# buseds-hab.net
KiCad netlist of a schematic drawn in EAGLE
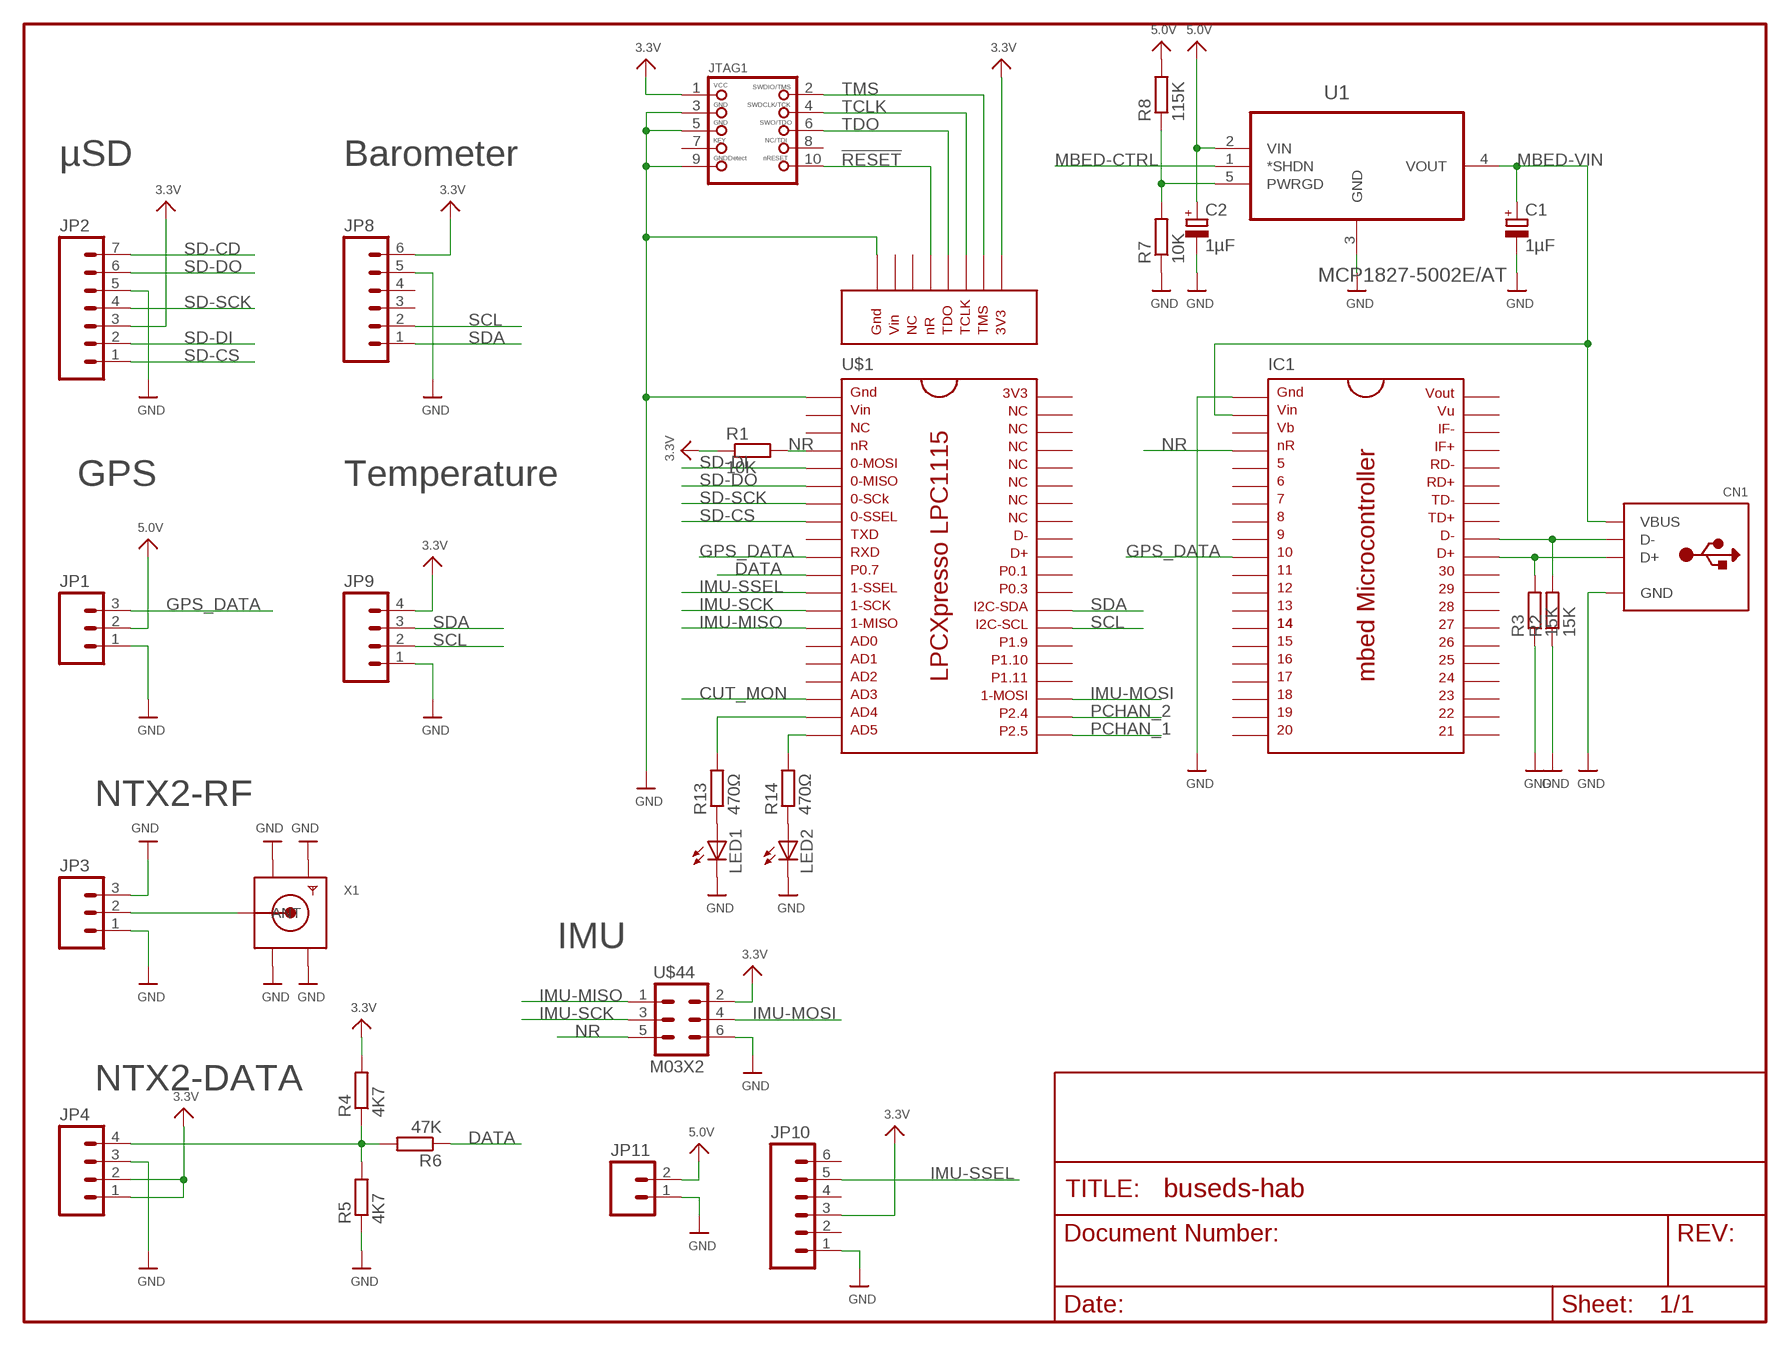
[diagram p0: schematic, sheet 1, part 1 of 2]
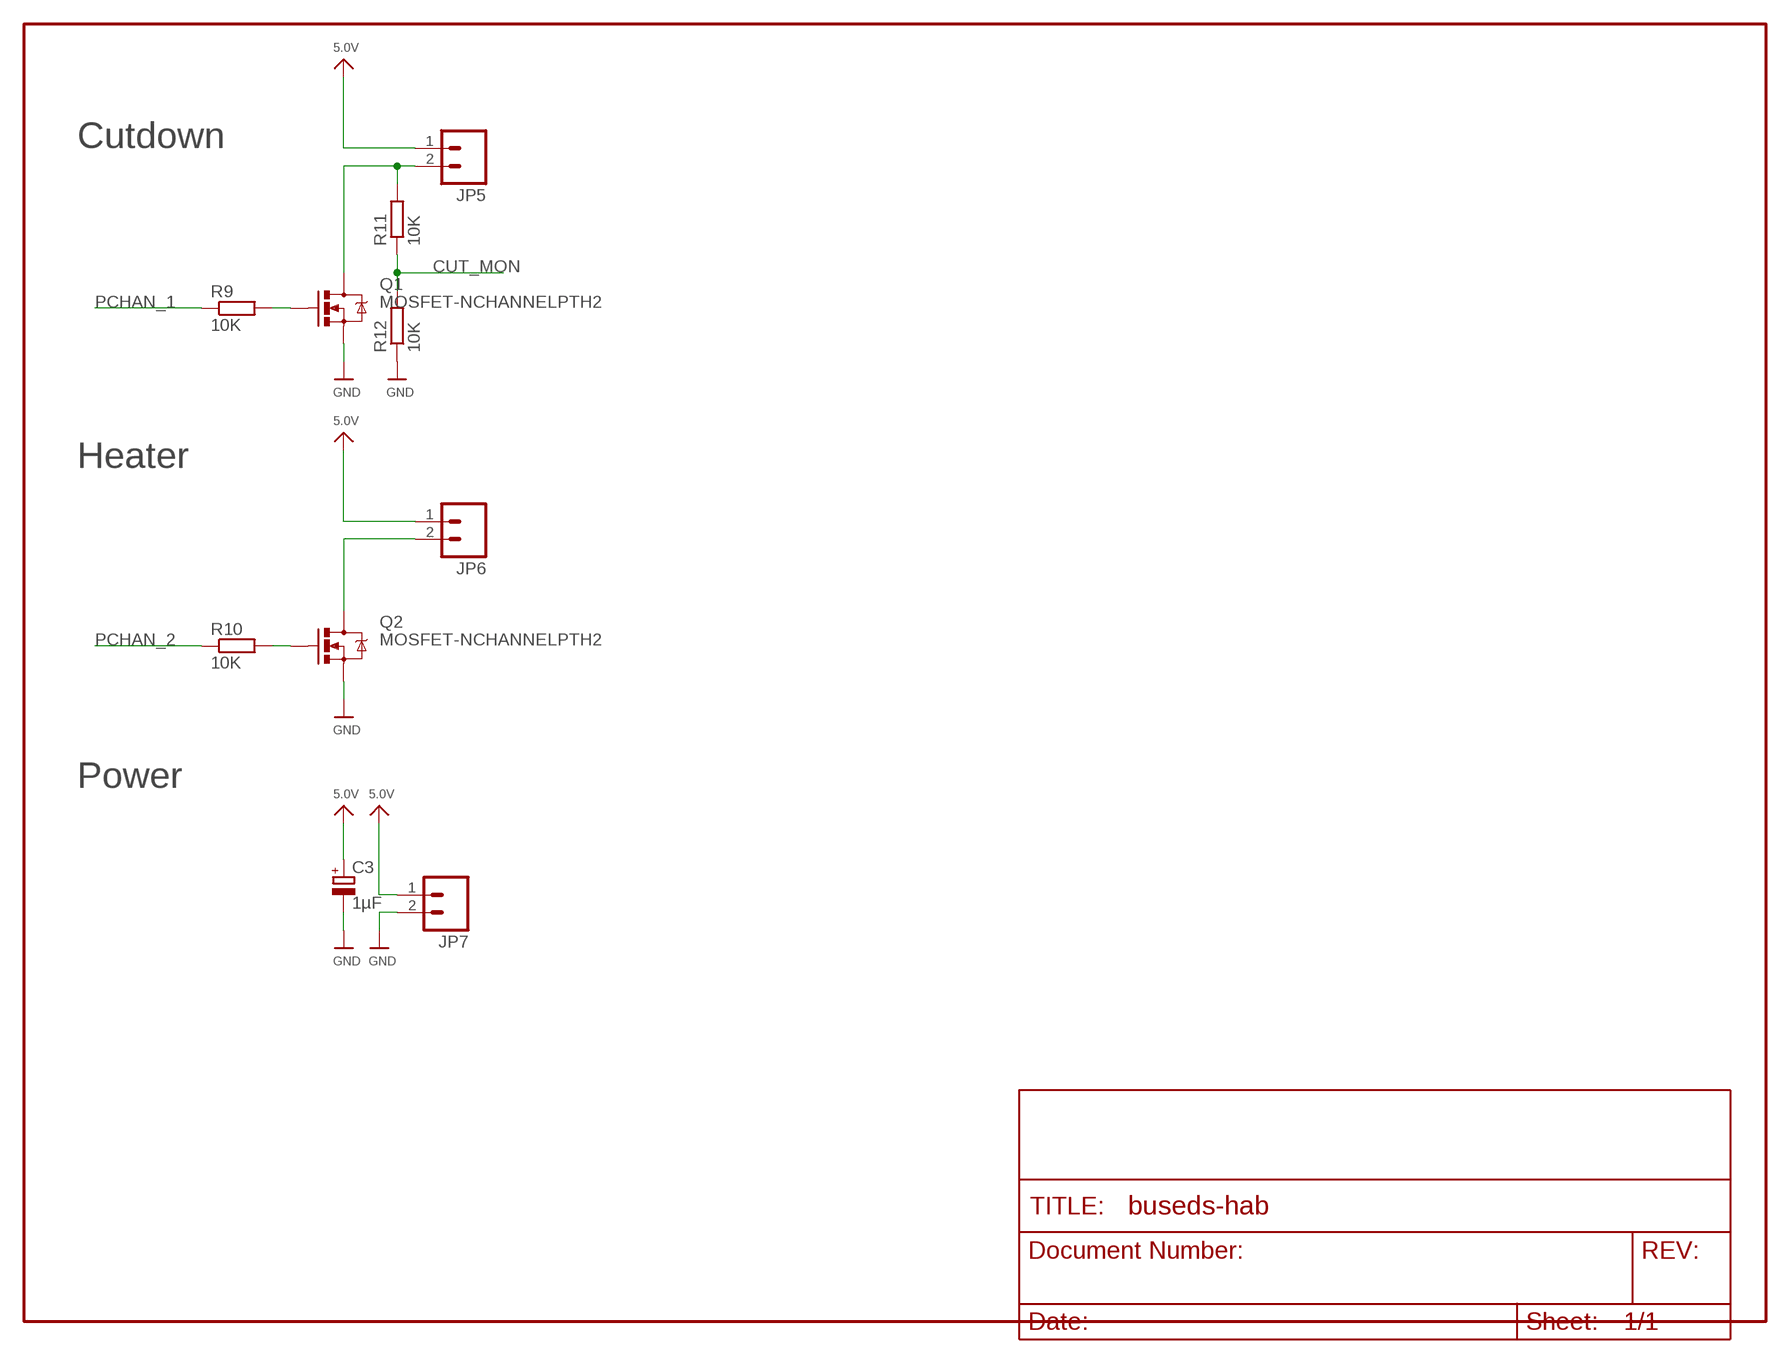
[diagram p1: schematic, sheet 1, part 2 of 2]

(export (version "E")
  (design (tool "Eeschema 10.0.6"))
  (components
    (comp (ref "C1")
      (value "1µF")
      (footprint "eagle-import:E2-5")
      (libsource (lib "eagle-import") (part "CPOL-EUE2-5"))
    )
    (comp (ref "C2")
      (value "1µF")
      (footprint "eagle-import:E2-5")
      (libsource (lib "eagle-import") (part "CPOL-EUE2-5"))
    )
    (comp (ref "C3")
      (value "1µF")
      (footprint "eagle-import:E2-5")
      (libsource (lib "eagle-import") (part "CPOL-EUE2-5"))
    )
    (comp (ref "CN1")
      (value "USB_TYPEAPTHFML")
      (footprint "eagle-import:USB_HOST-PTH")
      (libsource (lib "eagle-import") (part "USB_TYPEAPTHFML"))
    )
    (comp (ref "IC1")
      (value "MBED")
      (footprint "eagle-import:DIL40_0.9")
      (libsource (lib "eagle-import") (part "MBED"))
    )
    (comp (ref "JP1")
      (value "M03LOCK")
      (footprint "eagle-import:1X03_LOCK")
      (libsource (lib "eagle-import") (part "M03LOCK"))
    )
    (comp (ref "JP2")
      (value "M07LOCK")
      (footprint "eagle-import:1X07_LOCK")
      (libsource (lib "eagle-import") (part "M07LOCK"))
    )
    (comp (ref "JP3")
      (value "M03LOCK")
      (footprint "eagle-import:1X03_LOCK")
      (libsource (lib "eagle-import") (part "M03LOCK"))
    )
    (comp (ref "JP4")
      (value "M04LOCK")
      (footprint "eagle-import:1X04_LOCK")
      (libsource (lib "eagle-import") (part "M04LOCK"))
    )
    (comp (ref "JP5")
      (value "M023.5MM_LOCK")
      (footprint "eagle-import:SCREWTERMINAL-3.5MM-2_LOCK")
      (libsource (lib "eagle-import") (part "M023.5MM_LOCK"))
    )
    (comp (ref "JP6")
      (value "M023.5MM_LOCK")
      (footprint "eagle-import:SCREWTERMINAL-3.5MM-2_LOCK")
      (libsource (lib "eagle-import") (part "M023.5MM_LOCK"))
    )
    (comp (ref "JP7")
      (value "M023.5MM_LOCK")
      (footprint "eagle-import:SCREWTERMINAL-3.5MM-2_LOCK")
      (libsource (lib "eagle-import") (part "M023.5MM_LOCK"))
    )
    (comp (ref "JP8")
      (value "M06LOCK")
      (footprint "eagle-import:1X06_LOCK")
      (libsource (lib "eagle-import") (part "M06LOCK"))
    )
    (comp (ref "JP9")
      (value "M04LOCK")
      (footprint "eagle-import:1X04_LOCK")
      (libsource (lib "eagle-import") (part "M04LOCK"))
    )
    (comp (ref "JP10")
      (value "M06LOCK")
      (footprint "eagle-import:1X06_LOCK")
      (libsource (lib "eagle-import") (part "M06LOCK"))
    )
    (comp (ref "JP11")
      (value "M02LOCK")
      (footprint "eagle-import:1X02_LOCK")
      (libsource (lib "eagle-import") (part "M02LOCK"))
    )
    (comp (ref "JTAG1")
      (value "JTAG-CORTEXM3")
      (footprint "eagle-import:2X05_1.27MM")
      (libsource (lib "eagle-import") (part "JTAG-CORTEXM3"))
    )
    (comp (ref "LED1")
      (value "LED3MM")
      (footprint "eagle-import:LED3MM")
      (libsource (lib "eagle-import") (part "LED3MM"))
    )
    (comp (ref "LED2")
      (value "LED3MM")
      (footprint "eagle-import:LED3MM")
      (libsource (lib "eagle-import") (part "LED3MM"))
    )
    (comp (ref "Q1")
      (value "MOSFET-NCHANNELPTH2")
      (footprint "eagle-import:TO220V")
      (libsource (lib "eagle-import") (part "MOSFET-NCHANNELPTH2"))
    )
    (comp (ref "Q2")
      (value "MOSFET-NCHANNELPTH2")
      (footprint "eagle-import:TO220V")
      (libsource (lib "eagle-import") (part "MOSFET-NCHANNELPTH2"))
    )
    (comp (ref "R1")
      (value "10K")
      (footprint "eagle-import:0204_7")
      (libsource (lib "eagle-import") (part "R-EU_0204/7"))
    )
    (comp (ref "R2")
      (value "15K")
      (footprint "eagle-import:0204_7")
      (libsource (lib "eagle-import") (part "R-EU_0204/7"))
    )
    (comp (ref "R3")
      (value "15K")
      (footprint "eagle-import:0204_7")
      (libsource (lib "eagle-import") (part "R-EU_0204/7"))
    )
    (comp (ref "R4")
      (value "4K7")
      (footprint "eagle-import:0204_7")
      (libsource (lib "eagle-import") (part "R-EU_0204/7"))
    )
    (comp (ref "R5")
      (value "4K7")
      (footprint "eagle-import:0204_7")
      (libsource (lib "eagle-import") (part "R-EU_0204/7"))
    )
    (comp (ref "R6")
      (value "47K")
      (footprint "eagle-import:0204_7")
      (libsource (lib "eagle-import") (part "R-EU_0204/7"))
    )
    (comp (ref "R7")
      (value "10K")
      (footprint "eagle-import:0204_7")
      (libsource (lib "eagle-import") (part "R-EU_0204/7"))
    )
    (comp (ref "R8")
      (value "115K")
      (footprint "eagle-import:0204_7")
      (libsource (lib "eagle-import") (part "R-EU_0204/7"))
    )
    (comp (ref "R9")
      (value "10K")
      (footprint "eagle-import:0204_7")
      (libsource (lib "eagle-import") (part "R-EU_0204/7"))
    )
    (comp (ref "R10")
      (value "10K")
      (footprint "eagle-import:0204_7")
      (libsource (lib "eagle-import") (part "R-EU_0204/7"))
    )
    (comp (ref "R11")
      (value "10K")
      (footprint "eagle-import:0204_7")
      (libsource (lib "eagle-import") (part "R-EU_0204/7"))
    )
    (comp (ref "R12")
      (value "10K")
      (footprint "eagle-import:0204_7")
      (libsource (lib "eagle-import") (part "R-EU_0204/7"))
    )
    (comp (ref "R13")
      (value "470Ω")
      (footprint "eagle-import:0204_7")
      (libsource (lib "eagle-import") (part "R-EU_0204/7"))
    )
    (comp (ref "R14")
      (value "470Ω")
      (footprint "eagle-import:0204_7")
      (libsource (lib "eagle-import") (part "R-EU_0204/7"))
    )
    (comp (ref "U$1")
      (value "LPCXPRESSOLPC")
      (footprint "eagle-import:LPCXPRESSO")
      (libsource (lib "eagle-import") (part "LPCXPRESSOLPC"))
    )
    (comp (ref "U$44")
      (value "M03X2")
      (footprint "eagle-import:2X3_LOCK")
      (libsource (lib "eagle-import") (part "M03X2"))
    )
    (comp (ref "U1")
      (value "MCP1827-5002E/AT")
      (footprint "eagle-import:TO170P482X1024X3124-5P")
      (libsource (lib "eagle-import") (part "MCP1827-5002E/AT"))
    )
    (comp (ref "X1")
      (value "SMACONNECTOR")
      (footprint "eagle-import:SMA90_DIP")
      (libsource (lib "eagle-import") (part "SMACONNECTOR"))
    )
  )
  (nets
    (net (code "1") (name "/CUT_MON") (class "Default")
      (node (ref "R11") (pin "1") (pinfunction "1_1") (pintype "passive"))
      (node (ref "R12") (pin "2") (pinfunction "2_2") (pintype "passive"))
      (node (ref "U$1") (pin "18") (pinfunction "P$18_18") (pintype "bidirectional"))
    )
    (net (code "2") (name "/DATA") (class "Default")
      (node (ref "R6") (pin "1") (pinfunction "1_1") (pintype "passive"))
      (node (ref "U$1") (pin "11") (pinfunction "P$11_11") (pintype "bidirectional"))
    )
    (net (code "3") (name "/GPS_DATA") (class "Default")
      (node (ref "IC1") (pin "10") (pinfunction "P$10_10") (pintype "bidirectional"))
      (node (ref "JP1") (pin "3") (pinfunction "3_3") (pintype "passive"))
      (node (ref "U$1") (pin "10") (pinfunction "P$10_10") (pintype "bidirectional"))
    )
    (net (code "4") (name "/IMU-MISO") (class "Default")
      (node (ref "U$1") (pin "14") (pinfunction "P$14_14") (pintype "bidirectional"))
      (node (ref "U$44") (pin "1") (pinfunction "1_1") (pintype "passive"))
    )
    (net (code "5") (name "/IMU-MOSI") (class "Default")
      (node (ref "U$1") (pin "23") (pinfunction "P$23_23") (pintype "bidirectional"))
      (node (ref "U$44") (pin "4") (pinfunction "4_4") (pintype "passive"))
    )
    (net (code "6") (name "/IMU-SCK") (class "Default")
      (node (ref "U$1") (pin "13") (pinfunction "P$13_13") (pintype "bidirectional"))
      (node (ref "U$44") (pin "3") (pinfunction "3_3") (pintype "passive"))
    )
    (net (code "7") (name "/IMU-SSEL") (class "Default")
      (node (ref "JP10") (pin "5") (pinfunction "5_5") (pintype "passive"))
      (node (ref "U$1") (pin "12") (pinfunction "P$12_12") (pintype "bidirectional"))
    )
    (net (code "8") (name "/MBED-CTRL") (class "Default")
      (node (ref "U1") (pin "1") (pinfunction "*SHDN_1") (pintype "input"))
    )
    (net (code "9") (name "/MBED-VIN") (class "Default")
      (node (ref "C1") (pin "+") (pinfunction "+_+") (pintype "passive"))
      (node (ref "CN1") (pin "VBUS") (pinfunction "VBUS_VBUS") (pintype "power_in"))
      (node (ref "IC1") (pin "2") (pinfunction "P$2_2") (pintype "bidirectional"))
      (node (ref "U1") (pin "4") (pinfunction "VOUT_4") (pintype "output"))
    )
    (net (code "10") (name "/NR") (class "Default")
      (node (ref "IC1") (pin "4") (pinfunction "P$4_4") (pintype "bidirectional"))
      (node (ref "R1") (pin "2") (pinfunction "2_2") (pintype "passive"))
      (node (ref "U$1") (pin "4") (pinfunction "P$4_4") (pintype "bidirectional"))
      (node (ref "U$44") (pin "5") (pinfunction "5_5") (pintype "passive"))
    )
    (net (code "11") (name "/PCHAN_1") (class "Default")
      (node (ref "R9") (pin "1") (pinfunction "1_1") (pintype "passive"))
      (node (ref "U$1") (pin "21") (pinfunction "P$21_21") (pintype "bidirectional"))
    )
    (net (code "12") (name "/PCHAN_2") (class "Default")
      (node (ref "R10") (pin "1") (pinfunction "1_1") (pintype "passive"))
      (node (ref "U$1") (pin "22") (pinfunction "P$22_22") (pintype "bidirectional"))
    )
    (net (code "13") (name "/SCL") (class "Default")
      (node (ref "JP8") (pin "2") (pinfunction "2_2") (pintype "passive"))
      (node (ref "JP9") (pin "2") (pinfunction "2_2") (pintype "passive"))
      (node (ref "U$1") (pin "27") (pinfunction "P$27_27") (pintype "bidirectional"))
    )
    (net (code "14") (name "/SD-CD") (class "Default")
      (node (ref "JP2") (pin "7") (pinfunction "7_7") (pintype "passive"))
    )
    (net (code "15") (name "/SD-CS") (class "Default")
      (node (ref "JP2") (pin "1") (pinfunction "1_1") (pintype "passive"))
      (node (ref "U$1") (pin "8") (pinfunction "P$8_8") (pintype "bidirectional"))
    )
    (net (code "16") (name "/SD-DI") (class "Default")
      (node (ref "JP2") (pin "2") (pinfunction "2_2") (pintype "passive"))
      (node (ref "U$1") (pin "5") (pinfunction "P$5_5") (pintype "bidirectional"))
    )
    (net (code "17") (name "/SD-DO") (class "Default")
      (node (ref "JP2") (pin "6") (pinfunction "6_6") (pintype "passive"))
      (node (ref "U$1") (pin "6") (pinfunction "P$6_6") (pintype "bidirectional"))
    )
    (net (code "18") (name "/SD-SCK") (class "Default")
      (node (ref "JP2") (pin "4") (pinfunction "4_4") (pintype "passive"))
      (node (ref "U$1") (pin "7") (pinfunction "P$7_7") (pintype "bidirectional"))
    )
    (net (code "19") (name "/SDA") (class "Default")
      (node (ref "JP8") (pin "1") (pinfunction "1_1") (pintype "passive"))
      (node (ref "JP9") (pin "3") (pinfunction "3_3") (pintype "passive"))
      (node (ref "U$1") (pin "28") (pinfunction "P$28_28") (pintype "bidirectional"))
    )
    (net (code "20") (name "/TCLK") (class "Default")
      (node (ref "JTAG1") (pin "4") (pinfunction "4_4") (pintype "passive"))
      (node (ref "U$1") (pin "P-3") (pinfunction "P-3_P-3") (pintype "bidirectional"))
    )
    (net (code "21") (name "/TDO") (class "Default")
      (node (ref "JTAG1") (pin "6") (pinfunction "6_6") (pintype "passive"))
      (node (ref "U$1") (pin "P-4") (pinfunction "P-4_P-4") (pintype "bidirectional"))
    )
    (net (code "22") (name "/TMS") (class "Default")
      (node (ref "JTAG1") (pin "2") (pinfunction "2_2") (pintype "passive"))
      (node (ref "U$1") (pin "P-2") (pinfunction "P-2_P-2") (pintype "bidirectional"))
    )
    (net (code "23") (name "/~{RESET}") (class "Default")
      (node (ref "JTAG1") (pin "10") (pinfunction "10_10") (pintype "passive"))
      (node (ref "U$1") (pin "P-5") (pinfunction "P-5_P-5") (pintype "bidirectional"))
    )
    (net (code "24") (name "3.3V") (class "Default")
      (node (ref "JP10") (pin "3") (pinfunction "3_3") (pintype "passive"))
      (node (ref "JP2") (pin "3") (pinfunction "3_3") (pintype "passive"))
      (node (ref "JP4") (pin "1") (pinfunction "1_1") (pintype "passive"))
      (node (ref "JP4") (pin "2") (pinfunction "2_2") (pintype "passive"))
      (node (ref "JP8") (pin "6") (pinfunction "6_6") (pintype "passive"))
      (node (ref "JP9") (pin "4") (pinfunction "4_4") (pintype "passive"))
      (node (ref "JTAG1") (pin "1") (pinfunction "1_1") (pintype "passive"))
      (node (ref "R1") (pin "1") (pinfunction "1_1") (pintype "passive"))
      (node (ref "R4") (pin "2") (pinfunction "2_2") (pintype "passive"))
      (node (ref "U$1") (pin "P-1") (pinfunction "P-1_P-1") (pintype "bidirectional"))
      (node (ref "U$44") (pin "2") (pinfunction "2_2") (pintype "passive"))
    )
    (net (code "25") (name "5.0V") (class "Default")
      (node (ref "C2") (pin "+") (pinfunction "+_+") (pintype "passive"))
      (node (ref "C3") (pin "+") (pinfunction "+_+") (pintype "passive"))
      (node (ref "JP1") (pin "2") (pinfunction "2_2") (pintype "passive"))
      (node (ref "JP11") (pin "2") (pinfunction "2_2") (pintype "passive"))
      (node (ref "JP5") (pin "1") (pinfunction "1_1") (pintype "passive"))
      (node (ref "JP6") (pin "1") (pinfunction "1_1") (pintype "passive"))
      (node (ref "JP7") (pin "1") (pinfunction "1_1") (pintype "passive"))
      (node (ref "R8") (pin "2") (pinfunction "2_2") (pintype "passive"))
      (node (ref "U1") (pin "2") (pinfunction "VIN_2") (pintype "input"))
    )
    (net (code "26") (name "GND") (class "Default")
      (node (ref "C1") (pin "-") (pinfunction "-_-") (pintype "passive"))
      (node (ref "C2") (pin "-") (pinfunction "-_-") (pintype "passive"))
      (node (ref "C3") (pin "-") (pinfunction "-_-") (pintype "passive"))
      (node (ref "CN1") (pin "GND") (pinfunction "GND_GND") (pintype "power_in"))
      (node (ref "IC1") (pin "1") (pinfunction "P$1_1") (pintype "bidirectional"))
      (node (ref "JP1") (pin "1") (pinfunction "1_1") (pintype "passive"))
      (node (ref "JP10") (pin "1") (pinfunction "1_1") (pintype "passive"))
      (node (ref "JP11") (pin "1") (pinfunction "1_1") (pintype "passive"))
      (node (ref "JP2") (pin "5") (pinfunction "5_5") (pintype "passive"))
      (node (ref "JP3") (pin "1") (pinfunction "1_1") (pintype "passive"))
      (node (ref "JP3") (pin "3") (pinfunction "3_3") (pintype "passive"))
      (node (ref "JP4") (pin "3") (pinfunction "3_3") (pintype "passive"))
      (node (ref "JP7") (pin "2") (pinfunction "2_2") (pintype "passive"))
      (node (ref "JP8") (pin "5") (pinfunction "5_5") (pintype "passive"))
      (node (ref "JP9") (pin "1") (pinfunction "1_1") (pintype "passive"))
      (node (ref "JTAG1") (pin "3") (pinfunction "3_3") (pintype "passive"))
      (node (ref "JTAG1") (pin "5") (pinfunction "5_5") (pintype "passive"))
      (node (ref "JTAG1") (pin "9") (pinfunction "9_9") (pintype "passive"))
      (node (ref "LED1") (pin "K") (pinfunction "C_K") (pintype "passive"))
      (node (ref "LED2") (pin "K") (pinfunction "C_K") (pintype "passive"))
      (node (ref "Q1") (pin "3") (pinfunction "S_3") (pintype "passive"))
      (node (ref "Q2") (pin "3") (pinfunction "S_3") (pintype "passive"))
      (node (ref "R12") (pin "1") (pinfunction "1_1") (pintype "passive"))
      (node (ref "R2") (pin "1") (pinfunction "1_1") (pintype "passive"))
      (node (ref "R3") (pin "1") (pinfunction "1_1") (pintype "passive"))
      (node (ref "R5") (pin "1") (pinfunction "1_1") (pintype "passive"))
      (node (ref "R7") (pin "1") (pinfunction "1_1") (pintype "passive"))
      (node (ref "U$1") (pin "1") (pinfunction "P$1_1") (pintype "bidirectional"))
      (node (ref "U$1") (pin "P-8") (pinfunction "P-8_P-8") (pintype "bidirectional"))
      (node (ref "U$44") (pin "6") (pinfunction "6_6") (pintype "passive"))
      (node (ref "U1") (pin "3") (pinfunction "GND_3") (pintype "passive"))
      (node (ref "X1") (pin "GND1") (pinfunction "GND1_GND1") (pintype "power_in"))
      (node (ref "X1") (pin "GND2") (pinfunction "GND2_GND2") (pintype "power_in"))
      (node (ref "X1") (pin "GND3") (pinfunction "GND3_GND3") (pintype "power_in"))
      (node (ref "X1") (pin "GND4") (pinfunction "GND4_GND4") (pintype "power_in"))
    )
    (net (code "27") (name "Net-(IC1-P$31)") (class "Default")
      (node (ref "CN1") (pin "D+") (pinfunction "D+_D+") (pintype "bidirectional"))
      (node (ref "IC1") (pin "31") (pinfunction "P$31_31") (pintype "bidirectional"))
      (node (ref "R3") (pin "2") (pinfunction "2_2") (pintype "passive"))
    )
    (net (code "28") (name "Net-(IC1-P$32)") (class "Default")
      (node (ref "CN1") (pin "D-") (pinfunction "D-_D-") (pintype "bidirectional"))
      (node (ref "IC1") (pin "32") (pinfunction "P$32_32") (pintype "bidirectional"))
      (node (ref "R2") (pin "2") (pinfunction "2_2") (pintype "passive"))
    )
    (net (code "29") (name "Net-(JP4-Pad4)") (class "Default")
      (node (ref "JP4") (pin "4") (pinfunction "4_4") (pintype "passive"))
      (node (ref "R4") (pin "1") (pinfunction "1_1") (pintype "passive"))
      (node (ref "R5") (pin "2") (pinfunction "2_2") (pintype "passive"))
      (node (ref "R6") (pin "2") (pinfunction "2_2") (pintype "passive"))
    )
    (net (code "30") (name "Net-(LED1-PadA)") (class "Default")
      (node (ref "LED1") (pin "A") (pinfunction "A_A") (pintype "passive"))
      (node (ref "R13") (pin "1") (pinfunction "1_1") (pintype "passive"))
    )
    (net (code "31") (name "Net-(LED2-PadA)") (class "Default")
      (node (ref "LED2") (pin "A") (pinfunction "A_A") (pintype "passive"))
      (node (ref "R14") (pin "1") (pinfunction "1_1") (pintype "passive"))
    )
    (net (code "32") (name "Net-(Q1-D)") (class "Default")
      (node (ref "JP5") (pin "2") (pinfunction "2_2") (pintype "passive"))
      (node (ref "Q1") (pin "2") (pinfunction "D_2") (pintype "passive"))
      (node (ref "R11") (pin "2") (pinfunction "2_2") (pintype "passive"))
    )
    (net (code "33") (name "Net-(Q1-G)") (class "Default")
      (node (ref "Q1") (pin "1") (pinfunction "G_1") (pintype "passive"))
      (node (ref "R9") (pin "2") (pinfunction "2_2") (pintype "passive"))
    )
    (net (code "34") (name "Net-(Q2-D)") (class "Default")
      (node (ref "JP6") (pin "2") (pinfunction "2_2") (pintype "passive"))
      (node (ref "Q2") (pin "2") (pinfunction "D_2") (pintype "passive"))
    )
    (net (code "35") (name "Net-(Q2-G)") (class "Default")
      (node (ref "Q2") (pin "1") (pinfunction "G_1") (pintype "passive"))
      (node (ref "R10") (pin "2") (pinfunction "2_2") (pintype "passive"))
    )
    (net (code "36") (name "Net-(U$1-P$19)") (class "Default")
      (node (ref "R13") (pin "2") (pinfunction "2_2") (pintype "passive"))
      (node (ref "U$1") (pin "19") (pinfunction "P$19_19") (pintype "bidirectional"))
    )
    (net (code "37") (name "Net-(U$1-P$20)") (class "Default")
      (node (ref "R14") (pin "2") (pinfunction "2_2") (pintype "passive"))
      (node (ref "U$1") (pin "20") (pinfunction "P$20_20") (pintype "bidirectional"))
    )
    (net (code "38") (name "Net-(U1-PWRGD)") (class "Default")
      (node (ref "R7") (pin "2") (pinfunction "2_2") (pintype "passive"))
      (node (ref "R8") (pin "1") (pinfunction "1_1") (pintype "passive"))
      (node (ref "U1") (pin "5") (pinfunction "PWRGD_5") (pintype "input"))
    )
    (net (code "39") (name "Net-(X1-ANT)") (class "Default")
      (node (ref "JP3") (pin "2") (pinfunction "2_2") (pintype "passive"))
      (node (ref "X1") (pin "ANTENNA") (pinfunction "ANT_ANTENNA") (pintype "bidirectional"))
    )
    (net (code "40") (name "unconnected-(IC1-P$3-Pad3)") (class "Default")
      (node (ref "IC1") (pin "3") (pinfunction "P$3_3") (pintype "bidirectional"))
    )
    (net (code "41") (name "unconnected-(IC1-P$5-Pad5)") (class "Default")
      (node (ref "IC1") (pin "5") (pinfunction "P$5_5") (pintype "bidirectional"))
    )
    (net (code "42") (name "unconnected-(IC1-P$6-Pad6)") (class "Default")
      (node (ref "IC1") (pin "6") (pinfunction "P$6_6") (pintype "bidirectional"))
    )
    (net (code "43") (name "unconnected-(IC1-P$7-Pad7)") (class "Default")
      (node (ref "IC1") (pin "7") (pinfunction "P$7_7") (pintype "bidirectional"))
    )
    (net (code "44") (name "unconnected-(IC1-P$8-Pad8)") (class "Default")
      (node (ref "IC1") (pin "8") (pinfunction "P$8_8") (pintype "bidirectional"))
    )
    (net (code "45") (name "unconnected-(IC1-P$9-Pad9)") (class "Default")
      (node (ref "IC1") (pin "9") (pinfunction "P$9_9") (pintype "bidirectional"))
    )
    (net (code "46") (name "unconnected-(IC1-P$11-Pad11)") (class "Default")
      (node (ref "IC1") (pin "11") (pinfunction "P$11_11") (pintype "bidirectional"))
    )
    (net (code "47") (name "unconnected-(IC1-P$12-Pad12)") (class "Default")
      (node (ref "IC1") (pin "12") (pinfunction "P$12_12") (pintype "bidirectional"))
    )
    (net (code "48") (name "unconnected-(IC1-P$13-Pad13)") (class "Default")
      (node (ref "IC1") (pin "13") (pinfunction "P$13_13") (pintype "bidirectional"))
    )
    (net (code "49") (name "unconnected-(IC1-P$14-Pad14)") (class "Default")
      (node (ref "IC1") (pin "14") (pinfunction "P$14_14") (pintype "bidirectional"))
    )
    (net (code "50") (name "unconnected-(IC1-P$15-Pad15)") (class "Default")
      (node (ref "IC1") (pin "15") (pinfunction "P$15_15") (pintype "bidirectional"))
    )
    (net (code "51") (name "unconnected-(IC1-P$16-Pad16)") (class "Default")
      (node (ref "IC1") (pin "16") (pinfunction "P$16_16") (pintype "bidirectional"))
    )
    (net (code "52") (name "unconnected-(IC1-P$17-Pad17)") (class "Default")
      (node (ref "IC1") (pin "17") (pinfunction "P$17_17") (pintype "bidirectional"))
    )
    (net (code "53") (name "unconnected-(IC1-P$18-Pad18)") (class "Default")
      (node (ref "IC1") (pin "18") (pinfunction "P$18_18") (pintype "bidirectional"))
    )
    (net (code "54") (name "unconnected-(IC1-P$19-Pad19)") (class "Default")
      (node (ref "IC1") (pin "19") (pinfunction "P$19_19") (pintype "bidirectional"))
    )
    (net (code "55") (name "unconnected-(IC1-P$20-Pad20)") (class "Default")
      (node (ref "IC1") (pin "20") (pinfunction "P$20_20") (pintype "bidirectional"))
    )
    (net (code "56") (name "unconnected-(IC1-P$21-Pad21)") (class "Default")
      (node (ref "IC1") (pin "21") (pinfunction "P$21_21") (pintype "bidirectional"))
    )
    (net (code "57") (name "unconnected-(IC1-P$22-Pad22)") (class "Default")
      (node (ref "IC1") (pin "22") (pinfunction "P$22_22") (pintype "bidirectional"))
    )
    (net (code "58") (name "unconnected-(IC1-P$23-Pad23)") (class "Default")
      (node (ref "IC1") (pin "23") (pinfunction "P$23_23") (pintype "bidirectional"))
    )
    (net (code "59") (name "unconnected-(IC1-P$24-Pad24)") (class "Default")
      (node (ref "IC1") (pin "24") (pinfunction "P$24_24") (pintype "bidirectional"))
    )
    (net (code "60") (name "unconnected-(IC1-P$25-Pad25)") (class "Default")
      (node (ref "IC1") (pin "25") (pinfunction "P$25_25") (pintype "bidirectional"))
    )
    (net (code "61") (name "unconnected-(IC1-P$26-Pad26)") (class "Default")
      (node (ref "IC1") (pin "26") (pinfunction "P$26_26") (pintype "bidirectional"))
    )
    (net (code "62") (name "unconnected-(IC1-P$27-Pad27)") (class "Default")
      (node (ref "IC1") (pin "27") (pinfunction "P$27_27") (pintype "bidirectional"))
    )
    (net (code "63") (name "unconnected-(IC1-P$28-Pad28)") (class "Default")
      (node (ref "IC1") (pin "28") (pinfunction "P$28_28") (pintype "bidirectional"))
    )
    (net (code "64") (name "unconnected-(IC1-P$29-Pad29)") (class "Default")
      (node (ref "IC1") (pin "29") (pinfunction "P$29_29") (pintype "bidirectional"))
    )
    (net (code "65") (name "unconnected-(IC1-P$30-Pad30)") (class "Default")
      (node (ref "IC1") (pin "30") (pinfunction "P$30_30") (pintype "bidirectional"))
    )
    (net (code "66") (name "unconnected-(IC1-P$33-Pad33)") (class "Default")
      (node (ref "IC1") (pin "33") (pinfunction "P$33_33") (pintype "bidirectional"))
    )
    (net (code "67") (name "unconnected-(IC1-P$34-Pad34)") (class "Default")
      (node (ref "IC1") (pin "34") (pinfunction "P$34_34") (pintype "bidirectional"))
    )
    (net (code "68") (name "unconnected-(IC1-P$35-Pad35)") (class "Default")
      (node (ref "IC1") (pin "35") (pinfunction "P$35_35") (pintype "bidirectional"))
    )
    (net (code "69") (name "unconnected-(IC1-P$36-Pad36)") (class "Default")
      (node (ref "IC1") (pin "36") (pinfunction "P$36_36") (pintype "bidirectional"))
    )
    (net (code "70") (name "unconnected-(IC1-P$37-Pad37)") (class "Default")
      (node (ref "IC1") (pin "37") (pinfunction "P$37_37") (pintype "bidirectional"))
    )
    (net (code "71") (name "unconnected-(IC1-P$38-Pad38)") (class "Default")
      (node (ref "IC1") (pin "38") (pinfunction "P$38_38") (pintype "bidirectional"))
    )
    (net (code "72") (name "unconnected-(IC1-P$39-Pad39)") (class "Default")
      (node (ref "IC1") (pin "39") (pinfunction "P$39_39") (pintype "bidirectional"))
    )
    (net (code "73") (name "unconnected-(IC1-P$40-Pad40)") (class "Default")
      (node (ref "IC1") (pin "40") (pinfunction "P$40_40") (pintype "bidirectional"))
    )
    (net (code "74") (name "unconnected-(JP8-Pad3)") (class "Default")
      (node (ref "JP8") (pin "3") (pinfunction "3_3") (pintype "passive"))
    )
    (net (code "75") (name "unconnected-(JP8-Pad4)") (class "Default")
      (node (ref "JP8") (pin "4") (pinfunction "4_4") (pintype "passive"))
    )
    (net (code "76") (name "unconnected-(JP10-Pad2)") (class "Default")
      (node (ref "JP10") (pin "2") (pinfunction "2_2") (pintype "passive"))
    )
    (net (code "77") (name "unconnected-(JP10-Pad4)") (class "Default")
      (node (ref "JP10") (pin "4") (pinfunction "4_4") (pintype "passive"))
    )
    (net (code "78") (name "unconnected-(JP10-Pad6)") (class "Default")
      (node (ref "JP10") (pin "6") (pinfunction "6_6") (pintype "passive"))
    )
    (net (code "79") (name "unconnected-(JTAG1-Pad7)") (class "Default")
      (node (ref "JTAG1") (pin "7") (pinfunction "7_7") (pintype "passive"))
    )
    (net (code "80") (name "unconnected-(JTAG1-Pad8)") (class "Default")
      (node (ref "JTAG1") (pin "8") (pinfunction "8_8") (pintype "passive"))
    )
    (net (code "81") (name "unconnected-(U$1-P$2-Pad2)") (class "Default")
      (node (ref "U$1") (pin "2") (pinfunction "P$2_2") (pintype "bidirectional"))
    )
    (net (code "82") (name "unconnected-(U$1-P$3-Pad3)") (class "Default")
      (node (ref "U$1") (pin "3") (pinfunction "P$3_3") (pintype "bidirectional"))
    )
    (net (code "83") (name "unconnected-(U$1-P$9-Pad9)") (class "Default")
      (node (ref "U$1") (pin "9") (pinfunction "P$9_9") (pintype "bidirectional"))
    )
    (net (code "84") (name "unconnected-(U$1-P$15-Pad15)") (class "Default")
      (node (ref "U$1") (pin "15") (pinfunction "P$15_15") (pintype "bidirectional"))
    )
    (net (code "85") (name "unconnected-(U$1-P$16-Pad16)") (class "Default")
      (node (ref "U$1") (pin "16") (pinfunction "P$16_16") (pintype "bidirectional"))
    )
    (net (code "86") (name "unconnected-(U$1-P$17-Pad17)") (class "Default")
      (node (ref "U$1") (pin "17") (pinfunction "P$17_17") (pintype "bidirectional"))
    )
    (net (code "87") (name "unconnected-(U$1-P$24-Pad24)") (class "Default")
      (node (ref "U$1") (pin "24") (pinfunction "P$24_24") (pintype "bidirectional"))
    )
    (net (code "88") (name "unconnected-(U$1-P$25-Pad25)") (class "Default")
      (node (ref "U$1") (pin "25") (pinfunction "P$25_25") (pintype "bidirectional"))
    )
    (net (code "89") (name "unconnected-(U$1-P$26-Pad26)") (class "Default")
      (node (ref "U$1") (pin "26") (pinfunction "P$26_26") (pintype "bidirectional"))
    )
    (net (code "90") (name "unconnected-(U$1-P$29-Pad29)") (class "Default")
      (node (ref "U$1") (pin "29") (pinfunction "P$29_29") (pintype "bidirectional"))
    )
    (net (code "91") (name "unconnected-(U$1-P$30-Pad30)") (class "Default")
      (node (ref "U$1") (pin "30") (pinfunction "P$30_30") (pintype "bidirectional"))
    )
    (net (code "92") (name "unconnected-(U$1-P$31-Pad31)") (class "Default")
      (node (ref "U$1") (pin "31") (pinfunction "P$31_31") (pintype "bidirectional"))
    )
    (net (code "93") (name "unconnected-(U$1-P$32-Pad32)") (class "Default")
      (node (ref "U$1") (pin "32") (pinfunction "P$32_32") (pintype "bidirectional"))
    )
    (net (code "94") (name "unconnected-(U$1-P$33-Pad33)") (class "Default")
      (node (ref "U$1") (pin "33") (pinfunction "P$33_33") (pintype "bidirectional"))
    )
    (net (code "95") (name "unconnected-(U$1-P$34-Pad34)") (class "Default")
      (node (ref "U$1") (pin "34") (pinfunction "P$34_34") (pintype "bidirectional"))
    )
    (net (code "96") (name "unconnected-(U$1-P$35-Pad35)") (class "Default")
      (node (ref "U$1") (pin "35") (pinfunction "P$35_35") (pintype "bidirectional"))
    )
    (net (code "97") (name "unconnected-(U$1-P$36-Pad36)") (class "Default")
      (node (ref "U$1") (pin "36") (pinfunction "P$36_36") (pintype "bidirectional"))
    )
    (net (code "98") (name "unconnected-(U$1-P$37-Pad37)") (class "Default")
      (node (ref "U$1") (pin "37") (pinfunction "P$37_37") (pintype "bidirectional"))
    )
    (net (code "99") (name "unconnected-(U$1-P$38-Pad38)") (class "Default")
      (node (ref "U$1") (pin "38") (pinfunction "P$38_38") (pintype "bidirectional"))
    )
    (net (code "100") (name "unconnected-(U$1-P$39-Pad39)") (class "Default")
      (node (ref "U$1") (pin "39") (pinfunction "P$39_39") (pintype "bidirectional"))
    )
    (net (code "101") (name "unconnected-(U$1-P$40-Pad40)") (class "Default")
      (node (ref "U$1") (pin "40") (pinfunction "P$40_40") (pintype "bidirectional"))
    )
    (net (code "102") (name "unconnected-(U$1-PadP-6)") (class "Default")
      (node (ref "U$1") (pin "P-6") (pinfunction "P-6_P-6") (pintype "bidirectional"))
    )
    (net (code "103") (name "unconnected-(U$1-PadP-7)") (class "Default")
      (node (ref "U$1") (pin "P-7") (pinfunction "P-7_P-7") (pintype "bidirectional"))
    )
  )
)
